# Main.net
KiCad netlist of a schematic drawn in Altium Designer
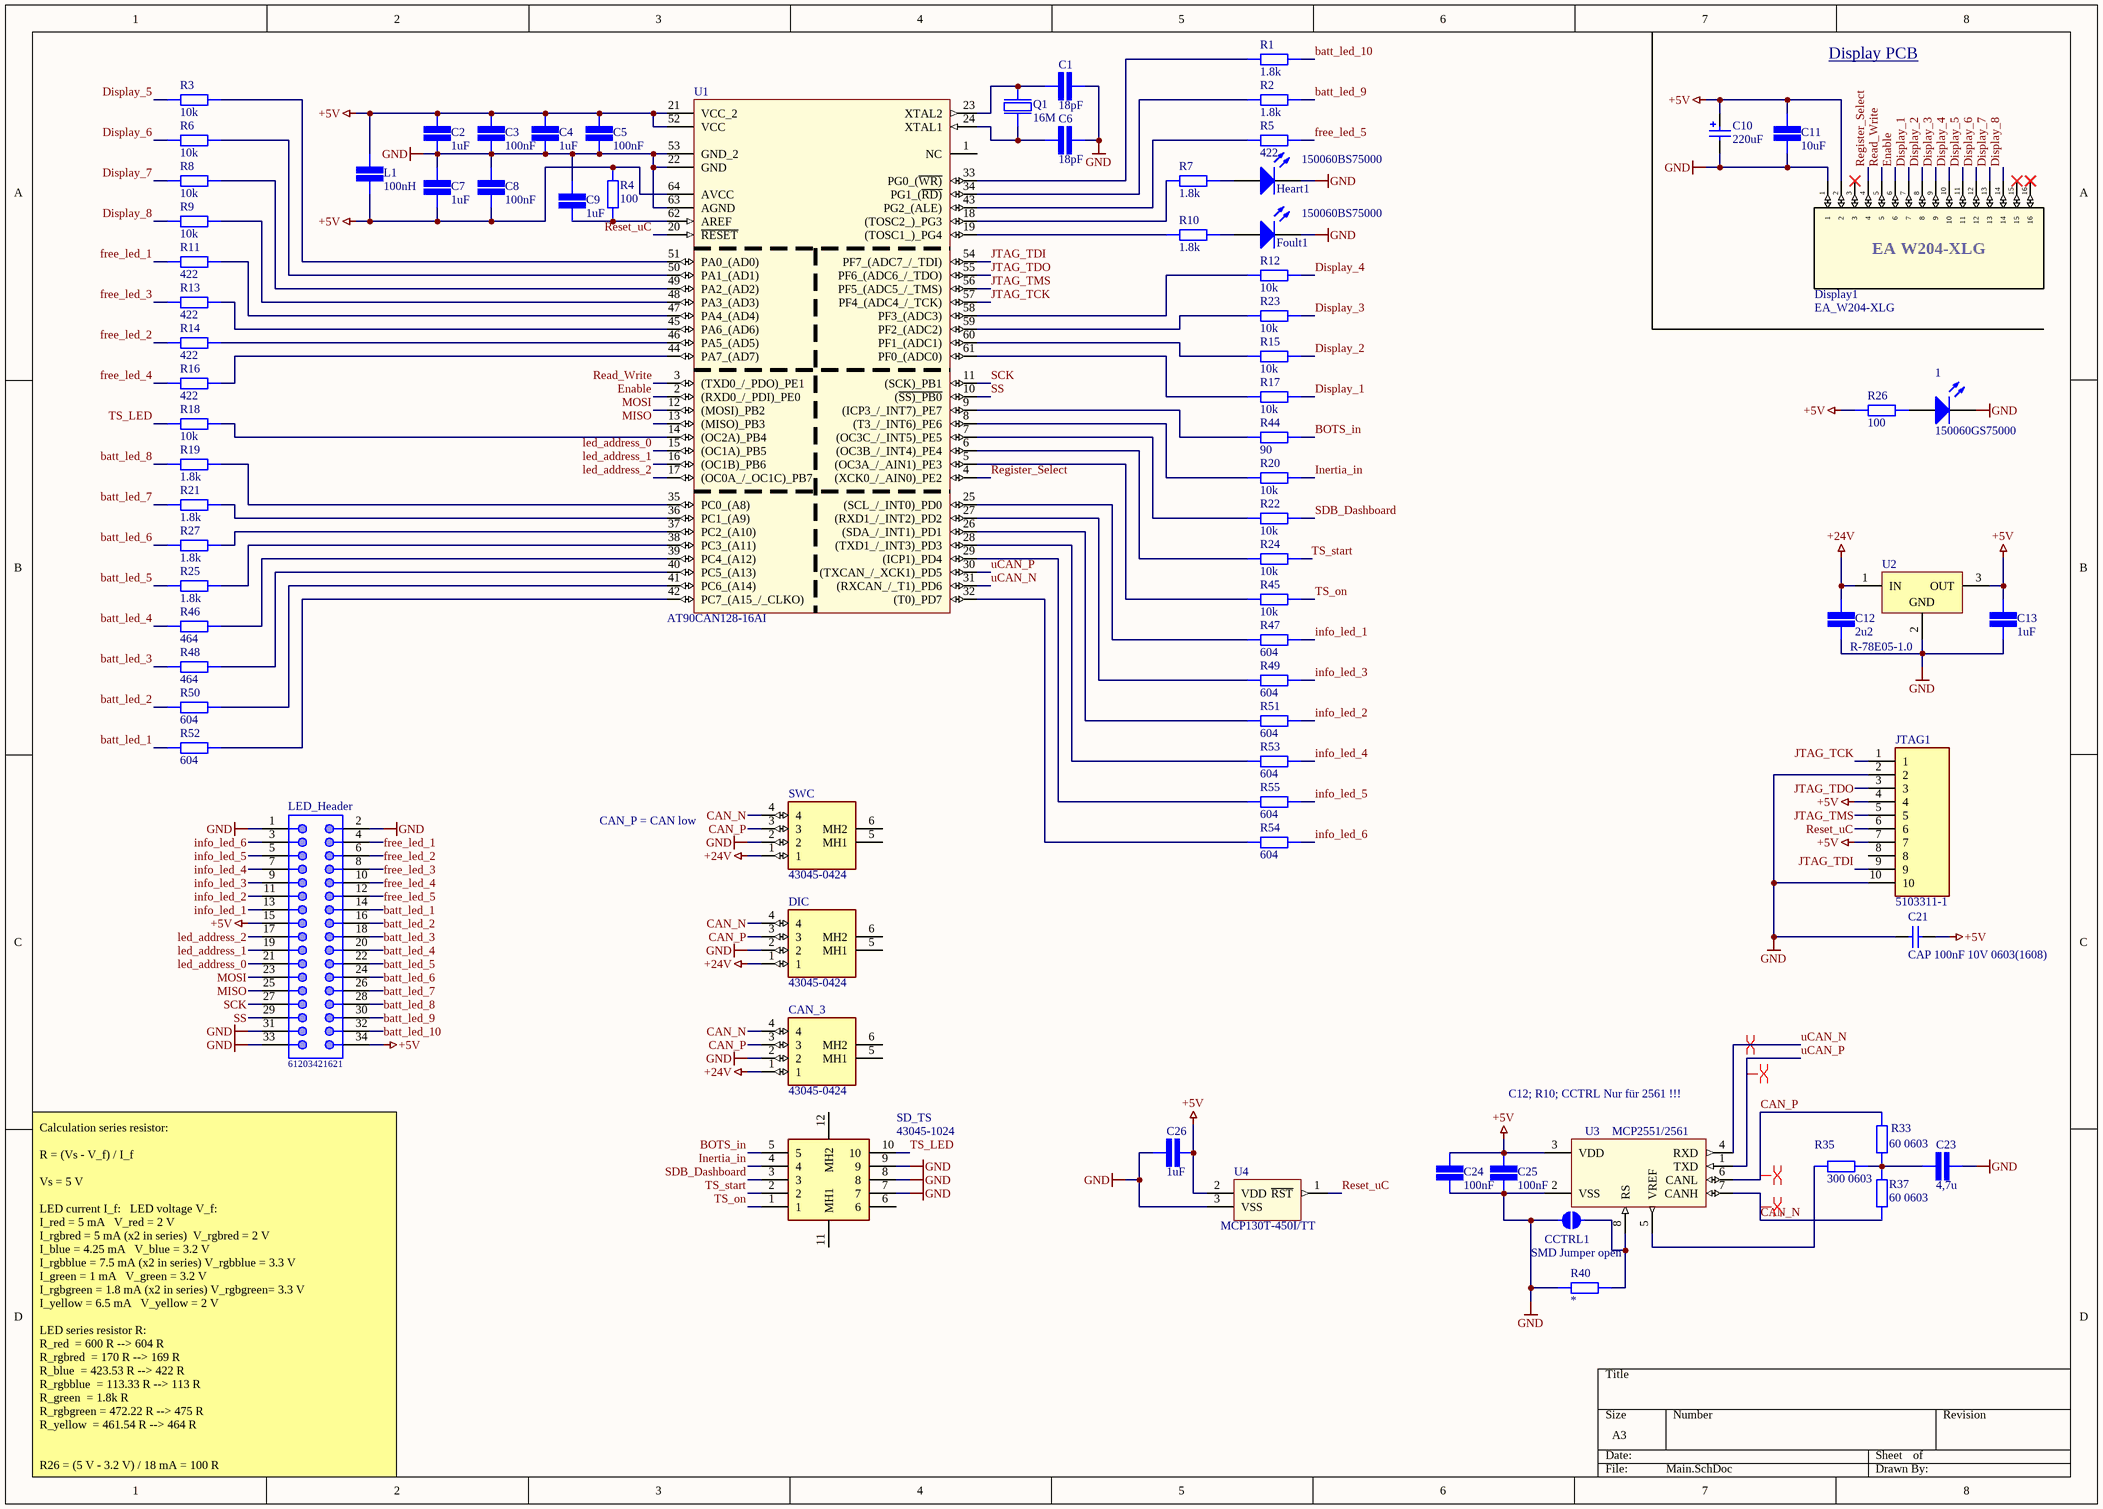
[diagram p0: Main.SchDoc]

(export (version "E")
  (design (tool "Eeschema 10.0.6"))
  (components
    (comp (ref "1")
      (value "150060GS75000")
      (footprint "0603_A")
      (description "SMD mono-color Chip LED, WL-SMCW, Green")
      (fields (field (name "MANUFACTURER") "Wuerth Elektronik"))
      (libsource (lib "Altium Content Vault") (part "WE-LED_K1A2-2"))
    )
    (comp (ref "C1")
      (value "18pF")
      (footprint "CAP 0603/1608")
      (description "Capacitor with multiple Footprints")
      (fields (field (name "Comment") "SMD Capacitor"))
      (libsource (lib "") (part "SMD Capacitor_2"))
    )
    (comp (ref "C2")
      (value "1uF")
      (footprint "CAP 0603/1608")
      (description "Capacitor with multiple Footprints")
      (fields (field (name "Comment") "SMD Capacitor"))
      (libsource (lib "Standardbauteile") (part "SMD Capacitor"))
    )
    (comp (ref "C3")
      (value "100nF")
      (footprint "CAP 0603/1608")
      (description "Capacitor with multiple Footprints")
      (fields (field (name "Comment") "SMD Capacitor"))
      (libsource (lib "Standardbauteile") (part "SMD Capacitor"))
    )
    (comp (ref "C4")
      (value "1uF")
      (footprint "CAP 0603/1608")
      (description "Capacitor with multiple Footprints")
      (fields (field (name "Comment") "SMD Capacitor"))
      (libsource (lib "Standardbauteile") (part "SMD Capacitor"))
    )
    (comp (ref "C5")
      (value "100nF")
      (footprint "CAP 0603/1608")
      (description "Capacitor with multiple Footprints")
      (fields (field (name "Comment") "SMD Capacitor"))
      (libsource (lib "Standardbauteile") (part "SMD Capacitor"))
    )
    (comp (ref "C6")
      (value "18pF")
      (footprint "CAP 0603/1608")
      (description "Capacitor with multiple Footprints")
      (fields (field (name "Comment") "SMD Capacitor"))
      (libsource (lib "") (part "SMD Capacitor_2"))
    )
    (comp (ref "C7")
      (value "1uF")
      (footprint "CAP 0603/1608")
      (description "Capacitor with multiple Footprints")
      (fields (field (name "Comment") "SMD Capacitor"))
      (libsource (lib "Standardbauteile") (part "SMD Capacitor"))
    )
    (comp (ref "C8")
      (value "100nF")
      (footprint "CAP 0603/1608")
      (description "Capacitor with multiple Footprints")
      (fields (field (name "Comment") "SMD Capacitor"))
      (libsource (lib "Standardbauteile") (part "SMD Capacitor"))
    )
    (comp (ref "C9")
      (value "1uF")
      (footprint "CAP 0603/1608")
      (description "Capacitor with multiple Footprints")
      (fields (field (name "Comment") "SMD Capacitor"))
      (libsource (lib "Standardbauteile") (part "SMD Capacitor"))
    )
    (comp (ref "C10")
      (value "220uF")
      (footprint "WCAP-ASLL_8x10.5")
      (description "WCAP-ASLL Aluminum Electrolytic Capacitors, size Ф8x10.5mm, 25V DC, 220uF")
      (fields (field (name "PART NUMBER") "865060453007") (field (name "PUBLISHER") "Wurth Elektronik"))
      (libsource (lib "ALTIUM-WCAP-ASLL-rev17a") (part "865060453007"))
    )
    (comp (ref "C11")
      (value "10uF")
      (footprint "CAP 0603/1608")
      (description "Capacitor with multiple Footprints")
      (fields (field (name "Comment") "SMD Capacitor"))
      (libsource (lib "") (part "SMD Capacitor_1"))
    )
    (comp (ref "C12")
      (value "2u2")
      (footprint "CAP 0603/1608")
      (description "Capacitor with multiple Footprints")
      (fields (field (name "Comment") "SMD Capacitor"))
      (libsource (lib "Standardbauteile") (part "SMD Capacitor"))
    )
    (comp (ref "C13")
      (value "1uF")
      (footprint "CAP 0603/1608")
      (description "Capacitor with multiple Footprints")
      (fields (field (name "Comment") "SMD Capacitor"))
      (libsource (lib "Standardbauteile") (part "SMD Capacitor"))
    )
    (comp (ref "C21")
      (value "CAP 100nF 10V 0603(1608)")
      (footprint "CAPC0603(1608)100_L")
      (description "CAP 100nF 10V ±5% 0603 (1608 Metric) Thickness 1mm SMD")
      (fields (field (name "TOLERANCE") "Â±5%"))
      (libsource (lib "Altium Content Vault") (part "CAP"))
    )
    (comp (ref "C23")
      (value "4,7u")
      (footprint "CAP 0603/1608")
      (description "Capacitor with multiple Footprints")
      (fields (field (name "Comment") "SMD Capacitor"))
      (libsource (lib "") (part "SMD Capacitor_3"))
    )
    (comp (ref "C24")
      (value "100nF")
      (footprint "CAP 0603/1608")
      (description "Capacitor with multiple Footprints")
      (fields (field (name "Comment") "SMD Capacitor"))
      (libsource (lib "Standardbauteile") (part "SMD Capacitor"))
    )
    (comp (ref "C25")
      (value "100nF")
      (footprint "CAP 0603/1608")
      (description "Capacitor with multiple Footprints")
      (fields (field (name "Comment") "SMD Capacitor"))
      (libsource (lib "Standardbauteile") (part "SMD Capacitor"))
    )
    (comp (ref "C26")
      (value "1uF")
      (footprint "CAP 0603/1608")
      (description "Capacitor with multiple Footprints")
      (fields (field (name "Comment") "SMD Capacitor"))
      (libsource (lib "") (part "SMD Capacitor_2"))
    )
    (comp (ref "CAN_3")
      (value "43045-0424")
      (footprint "43045-0424")
      (description "Connector Wire to Board Header 4 Position 3mm Solder Straight Thru-Hole Tray")
      (fields (field (name "MANUFACTURER") "Molex"))
      (libsource (lib "molex_43045") (part "43045-0424"))
    )
    (comp (ref "CCTRL1")
      (value "SMD Jumper open")
      (footprint "SMD-JUMPER-OPEN")
      (libsource (lib "Standardbauteile") (part "SMD Jumper open"))
    )
    (comp (ref "DIC")
      (value "43045-0424")
      (footprint "43045-0424")
      (description "Connector Wire to Board Header 4 Position 3mm Solder Straight Thru-Hole Tray")
      (fields (field (name "MANUFACTURER") "Molex"))
      (libsource (lib "molex_43045") (part "43045-0424"))
    )
    (comp (ref "Display1")
      (value "EA_W204-XLG")
      (footprint "EA_W204-XLG")
      (description "Display")
      (libsource (lib "libNico") (part "EA_W204-XLG"))
    )
    (comp (ref "Foult1")
      (value "150060BS75000")
      (footprint "0603_A")
      (description "SMD mono-color Chip LED, WL-SMCW, Blue")
      (fields (field (name "MANUFACTURER") "Wuerth Elektronik"))
      (libsource (lib "Altium Content Vault") (part "WE-LED_K1A2-2"))
    )
    (comp (ref "Heart1")
      (value "150060BS75000")
      (footprint "0603_A")
      (description "SMD mono-color Chip LED, WL-SMCW, Blue")
      (fields (field (name "MANUFACTURER") "Wuerth Elektronik"))
      (libsource (lib "Altium Content Vault") (part "WE-LED_K1A2-2"))
    )
    (comp (ref "JTAG1")
      (value "5103311-1")
      (footprint "TE_5103311-1")
      (description "AMP-LATCH Pin Header, Low Profile, 10 Pos., Right Angle PCB Mount, .100 X .100")
      (fields (field (name "MF") "TE Connectivity"))
      (libsource (lib "5103311-1") (part "5103311-1"))
    )
    (comp (ref "L1")
      (value "100nH")
      (footprint "CAP 0603/1608")
      (description "Capacitor with multiple Footprints")
      (fields (field (name "Comment") "SMD Capacitor"))
      (libsource (lib "Standardbauteile") (part "SMD Capacitor"))
    )
    (comp (ref "LED_Header")
      (value "61203421621")
      (footprint "61203421621")
      (description "WR-BHD Box Header, Male PCB side, pitch 2.54mm, THT, Straight, 34p")
      (fields (field (name "MANUFACTURER") "Wurth Elektronik"))
      (libsource (lib "Altium_WR-BHD (rev21a)") (part "61203421621"))
    )
    (comp (ref "Q1")
      (value "16M")
      (footprint "NDK NX5032GA")
      (description "16 MHz Quartz")
      (libsource (lib "Standardbauteile") (part "16 MHz Quartz"))
    )
    (comp (ref "R1")
      (value "1.8k")
      (footprint "STACKPOLE CSR0603")
      (description "Resistor with multiple footprints\r\n\r\n500R or 1kR depends on luminous intensity")
      (fields (field (name "Comment") "SMD Resistor"))
      (libsource (lib "Standardbauteile") (part "SMD Resistor"))
    )
    (comp (ref "R2")
      (value "1.8k")
      (footprint "STACKPOLE CSR0603")
      (description "Resistor with multiple footprints\r\n\r\n500R or 1kR depends on luminous intensity")
      (fields (field (name "Comment") "SMD Resistor"))
      (libsource (lib "Standardbauteile") (part "SMD Resistor"))
    )
    (comp (ref "R3")
      (value "10k")
      (footprint "STACKPOLE CSR0603")
      (description "Resistor with multiple footprints")
      (fields (field (name "Comment") "SMD Resistor"))
      (libsource (lib "Standardbauteile") (part "SMD Resistor"))
    )
    (comp (ref "R4")
      (value "100")
      (footprint "STACKPOLE CSR0603")
      (description "Resistor with multiple footprints")
      (fields (field (name "Comment") "SMD Resistor"))
      (libsource (lib "Standardbauteile") (part "SMD Resistor"))
    )
    (comp (ref "R5")
      (value "422")
      (footprint "STACKPOLE CSR0603")
      (description "Resistor with multiple footprints\r\n\r\n500R or 1kR depends on luminous intensity")
      (fields (field (name "Comment") "SMD Resistor"))
      (libsource (lib "Standardbauteile") (part "SMD Resistor"))
    )
    (comp (ref "R6")
      (value "10k")
      (footprint "STACKPOLE CSR0603")
      (description "Resistor with multiple footprints")
      (fields (field (name "Comment") "SMD Resistor"))
      (libsource (lib "Standardbauteile") (part "SMD Resistor"))
    )
    (comp (ref "R7")
      (value "1.8k")
      (footprint "STACKPOLE CSR0603")
      (description "Resistor with multiple footprints")
      (fields (field (name "Comment") "SMD Resistor"))
      (libsource (lib "Standardbauteile") (part "SMD Resistor"))
    )
    (comp (ref "R8")
      (value "10k")
      (footprint "STACKPOLE CSR0603")
      (description "Resistor with multiple footprints")
      (fields (field (name "Comment") "SMD Resistor"))
      (libsource (lib "Standardbauteile") (part "SMD Resistor"))
    )
    (comp (ref "R9")
      (value "10k")
      (footprint "STACKPOLE CSR0603")
      (description "Resistor with multiple footprints")
      (fields (field (name "Comment") "SMD Resistor"))
      (libsource (lib "Standardbauteile") (part "SMD Resistor"))
    )
    (comp (ref "R10")
      (value "1.8k")
      (footprint "STACKPOLE CSR0603")
      (description "Resistor with multiple footprints")
      (fields (field (name "Comment") "SMD Resistor"))
      (libsource (lib "Standardbauteile") (part "SMD Resistor"))
    )
    (comp (ref "R11")
      (value "422")
      (footprint "STACKPOLE CSR0603")
      (description "Resistor with multiple footprints\r\n\r\n500R or 1kR depends on luminous intensity")
      (fields (field (name "Comment") "SMD Resistor"))
      (libsource (lib "Standardbauteile") (part "SMD Resistor"))
    )
    (comp (ref "R12")
      (value "10k")
      (footprint "STACKPOLE CSR0603")
      (description "Resistor with multiple footprints")
      (fields (field (name "Comment") "SMD Resistor"))
      (libsource (lib "Standardbauteile") (part "SMD Resistor"))
    )
    (comp (ref "R13")
      (value "422")
      (footprint "STACKPOLE CSR0603")
      (description "Resistor with multiple footprints\r\n\r\n500R or 1kR depends on luminous intensity")
      (fields (field (name "Comment") "SMD Resistor"))
      (libsource (lib "Standardbauteile") (part "SMD Resistor"))
    )
    (comp (ref "R14")
      (value "422")
      (footprint "STACKPOLE CSR0603")
      (description "Resistor with multiple footprints\r\n\r\n500R or 1kR depends on luminous intensity")
      (fields (field (name "Comment") "SMD Resistor"))
      (libsource (lib "Standardbauteile") (part "SMD Resistor"))
    )
    (comp (ref "R15")
      (value "10k")
      (footprint "STACKPOLE CSR0603")
      (description "Resistor with multiple footprints")
      (fields (field (name "Comment") "SMD Resistor"))
      (libsource (lib "Standardbauteile") (part "SMD Resistor"))
    )
    (comp (ref "R16")
      (value "422")
      (footprint "STACKPOLE CSR0603")
      (description "Resistor with multiple footprints\r\n\r\n500R or 1kR depends on luminous intensity")
      (fields (field (name "Comment") "SMD Resistor"))
      (libsource (lib "Standardbauteile") (part "SMD Resistor"))
    )
    (comp (ref "R17")
      (value "10k")
      (footprint "STACKPOLE CSR0603")
      (description "Resistor with multiple footprints")
      (fields (field (name "Comment") "SMD Resistor"))
      (libsource (lib "Standardbauteile") (part "SMD Resistor"))
    )
    (comp (ref "R18")
      (value "10k")
      (footprint "STACKPOLE CSR0603")
      (description "Resistor with multiple footprints")
      (fields (field (name "Comment") "SMD Resistor"))
      (libsource (lib "Standardbauteile") (part "SMD Resistor"))
    )
    (comp (ref "R19")
      (value "1.8k")
      (footprint "STACKPOLE CSR0603")
      (description "Resistor with multiple footprints\r\n\r\n500R or 1kR depends on luminous intensity")
      (fields (field (name "Comment") "SMD Resistor"))
      (libsource (lib "Standardbauteile") (part "SMD Resistor"))
    )
    (comp (ref "R20")
      (value "10k")
      (footprint "STACKPOLE CSR0603")
      (description "Resistor with multiple footprints")
      (fields (field (name "Comment") "SMD Resistor"))
      (libsource (lib "Standardbauteile") (part "SMD Resistor"))
    )
    (comp (ref "R21")
      (value "1.8k")
      (footprint "STACKPOLE CSR0603")
      (description "Resistor with multiple footprints\r\n\r\n500R or 1kR depends on luminous intensity")
      (fields (field (name "Comment") "SMD Resistor"))
      (libsource (lib "Standardbauteile") (part "SMD Resistor"))
    )
    (comp (ref "R22")
      (value "10k")
      (footprint "STACKPOLE CSR0603")
      (description "Resistor with multiple footprints")
      (fields (field (name "Comment") "SMD Resistor"))
      (libsource (lib "Standardbauteile") (part "SMD Resistor"))
    )
    (comp (ref "R23")
      (value "10k")
      (footprint "STACKPOLE CSR0603")
      (description "Resistor with multiple footprints")
      (fields (field (name "Comment") "SMD Resistor"))
      (libsource (lib "Standardbauteile") (part "SMD Resistor"))
    )
    (comp (ref "R24")
      (value "10k")
      (footprint "STACKPOLE CSR0603")
      (description "Resistor with multiple footprints")
      (fields (field (name "Comment") "SMD Resistor"))
      (libsource (lib "Standardbauteile") (part "SMD Resistor"))
    )
    (comp (ref "R25")
      (value "1.8k")
      (footprint "STACKPOLE CSR0603")
      (description "Resistor with multiple footprints\r\n\r\n500R or 1kR depends on luminous intensity")
      (fields (field (name "Comment") "SMD Resistor"))
      (libsource (lib "Standardbauteile") (part "SMD Resistor"))
    )
    (comp (ref "R26")
      (value "100")
      (footprint "STACKPOLE CSR0603")
      (description "Resistor with multiple footprints")
      (fields (field (name "Comment") "SMD Resistor"))
      (libsource (lib "Standardbauteile") (part "SMD Resistor"))
    )
    (comp (ref "R27")
      (value "1.8k")
      (footprint "STACKPOLE CSR0603")
      (description "Resistor with multiple footprints\r\n\r\n500R or 1kR depends on luminous intensity")
      (fields (field (name "Comment") "SMD Resistor"))
      (libsource (lib "Standardbauteile") (part "SMD Resistor"))
    )
    (comp (ref "R33")
      (value "60 0603")
      (footprint "STACKPOLE CSR0603")
      (description "Resistor with multiple footprints")
      (fields (field (name "Comment") "SMD Resistor"))
      (libsource (lib "Standardbauteile") (part "SMD Resistor"))
    )
    (comp (ref "R35")
      (value "300 0603")
      (footprint "STACKPOLE CSR0603")
      (description "Resistor with multiple footprints")
      (fields (field (name "Comment") "SMD Resistor"))
      (libsource (lib "Standardbauteile") (part "SMD Resistor"))
    )
    (comp (ref "R37")
      (value "60 0603")
      (footprint "STACKPOLE CSR0603")
      (description "Resistor with multiple footprints")
      (fields (field (name "Comment") "SMD Resistor"))
      (libsource (lib "Standardbauteile") (part "SMD Resistor"))
    )
    (comp (ref "R40")
      (value "SMD Resistor")
      (footprint "STACKPOLE CSR0603")
      (description "Resistor with multiple footprints")
      (fields (field (name "ALTIUM_VALUE") "*"))
      (libsource (lib "Standardbauteile") (part "SMD Resistor"))
    )
    (comp (ref "R44")
      (value "90")
      (footprint "STACKPOLE CSR0603")
      (description "Resistor with multiple footprints\r\n\r\n500R or 1kR depends on luminous intensity")
      (fields (field (name "Comment") "SMD Resistor"))
      (libsource (lib "Standardbauteile") (part "SMD Resistor"))
    )
    (comp (ref "R45")
      (value "10k")
      (footprint "STACKPOLE CSR0603")
      (description "Resistor with multiple footprints")
      (fields (field (name "Comment") "SMD Resistor"))
      (libsource (lib "Standardbauteile") (part "SMD Resistor"))
    )
    (comp (ref "R46")
      (value "464")
      (footprint "STACKPOLE CSR0603")
      (description "Resistor with multiple footprints\r\n\r\n500R or 1kR depends on luminous intensity")
      (fields (field (name "Comment") "SMD Resistor"))
      (libsource (lib "Standardbauteile") (part "SMD Resistor"))
    )
    (comp (ref "R47")
      (value "604")
      (footprint "STACKPOLE CSR0603")
      (description "Resistor with multiple footprints")
      (fields (field (name "Comment") "SMD Resistor"))
      (libsource (lib "Standardbauteile") (part "SMD Resistor"))
    )
    (comp (ref "R48")
      (value "464")
      (footprint "STACKPOLE CSR0603")
      (description "Resistor with multiple footprints\r\n\r\n500R or 1kR depends on luminous intensity")
      (fields (field (name "Comment") "SMD Resistor"))
      (libsource (lib "Standardbauteile") (part "SMD Resistor"))
    )
    (comp (ref "R49")
      (value "604")
      (footprint "STACKPOLE CSR0603")
      (description "Resistor with multiple footprints")
      (fields (field (name "Comment") "SMD Resistor"))
      (libsource (lib "Standardbauteile") (part "SMD Resistor"))
    )
    (comp (ref "R50")
      (value "604")
      (footprint "STACKPOLE CSR0603")
      (description "Resistor with multiple footprints\r\n\r\n500R or 1kR depends on luminous intensity")
      (fields (field (name "Comment") "SMD Resistor"))
      (libsource (lib "Standardbauteile") (part "SMD Resistor"))
    )
    (comp (ref "R51")
      (value "604")
      (footprint "STACKPOLE CSR0603")
      (description "Resistor with multiple footprints")
      (fields (field (name "Comment") "SMD Resistor"))
      (libsource (lib "Standardbauteile") (part "SMD Resistor"))
    )
    (comp (ref "R52")
      (value "604")
      (footprint "STACKPOLE CSR0603")
      (description "Resistor with multiple footprints\r\n\r\n500R or 1kR depends on luminous intensity")
      (fields (field (name "Comment") "SMD Resistor"))
      (libsource (lib "Standardbauteile") (part "SMD Resistor"))
    )
    (comp (ref "R53")
      (value "604")
      (footprint "STACKPOLE CSR0603")
      (description "Resistor with multiple footprints")
      (fields (field (name "Comment") "SMD Resistor"))
      (libsource (lib "Standardbauteile") (part "SMD Resistor"))
    )
    (comp (ref "R54")
      (value "604")
      (footprint "STACKPOLE CSR0603")
      (description "Resistor with multiple footprints")
      (fields (field (name "Comment") "SMD Resistor"))
      (libsource (lib "Standardbauteile") (part "SMD Resistor"))
    )
    (comp (ref "R55")
      (value "604")
      (footprint "STACKPOLE CSR0603")
      (description "Resistor with multiple footprints")
      (fields (field (name "Comment") "SMD Resistor"))
      (libsource (lib "Standardbauteile") (part "SMD Resistor"))
    )
    (comp (ref "SD_TS")
      (value "43045-1024")
      (footprint "43045-1024")
      (description "Connector Wire to Board Header 10 Position 3mm Solder Straight Thru-Hole Tray")
      (fields (field (name "MANUFACTURER") "Molex"))
      (libsource (lib "molex_43045") (part "43045-1024"))
    )
    (comp (ref "SWC")
      (value "43045-0424")
      (footprint "43045-0424")
      (description "Connector Wire to Board Header 4 Position 3mm Solder Straight Thru-Hole Tray")
      (fields (field (name "MANUFACTURER") "Molex"))
      (libsource (lib "molex_43045") (part "43045-0424"))
    )
    (comp (ref "U1")
      (value "AT90CAN128-16AI")
      (footprint "*QFP80P1600X1600X120-64N")
      (description "Ic Mcu 8bit 128kb Flash 64tqfp")
      (fields (field (name "MF") "Microchip"))
      (libsource (lib "Eric") (part "AT90CAN128-16AI"))
    )
    (comp (ref "U2")
      (value "R-78E05-1.0")
      (footprint "SIP3_RECOM")
      (description "Nonisolated 5V Switchmode converter")
      (libsource (lib "Standardbauteile") (part "R-78E05-1.0"))
    )
    (comp (ref "U3")
      (value "MCP2551/2561")
      (footprint "*SOIC127P600X175-8N")
      (description "MCP2551 Series 5.5 V 1 Mb/s Surface Mount High-Speed CAN Transceiver - SOIC-8")
      (fields (field (name "MP") "MCP2551-I/SN") (field (name "MF") "Microchip"))
      (libsource (lib "Eric") (part "MCP2551-I/SN"))
    )
    (comp (ref "U4")
      (value "MCP130T-450I/TT")
      (footprint "*SOT95P237X112-3N")
      (description "System Supervisors - Power Supply Monitors with Reset Generators Open Drain Low")
      (fields (field (name "MF") "Microchip") (field (name "MP") "MCP120T-450I/TT"))
      (libsource (lib "Eric") (part "MCP130T-450I/TT"))
    )
  )
  (nets
    (net (code "1") (name "+5V") (class "Default")
      (node (ref "C10") (pin "1") (pinfunction "P_1") (pintype "passive"))
      (node (ref "C11") (pin "1") (pinfunction "1_1") (pintype "passive"))
      (node (ref "C13") (pin "2") (pinfunction "2_2") (pintype "passive"))
      (node (ref "C2") (pin "2") (pinfunction "2_2") (pintype "passive"))
      (node (ref "C21") (pin "1") (pinfunction "1_1") (pintype "passive"))
      (node (ref "C24") (pin "2") (pinfunction "2_2") (pintype "passive"))
      (node (ref "C25") (pin "2") (pinfunction "2_2") (pintype "passive"))
      (node (ref "C26") (pin "1") (pinfunction "1_1") (pintype "passive"))
      (node (ref "C3") (pin "2") (pinfunction "2_2") (pintype "passive"))
      (node (ref "C4") (pin "2") (pinfunction "2_2") (pintype "passive"))
      (node (ref "C5") (pin "2") (pinfunction "2_2") (pintype "passive"))
      (node (ref "C7") (pin "1") (pinfunction "1_1") (pintype "passive"))
      (node (ref "C8") (pin "1") (pinfunction "1_1") (pintype "passive"))
      (node (ref "Display1") (pin "2") (pinfunction "2_2") (pintype "bidirectional"))
      (node (ref "JTAG1") (pin "4") (pinfunction "4_4") (pintype "passive"))
      (node (ref "JTAG1") (pin "7") (pinfunction "7_7") (pintype "passive"))
      (node (ref "L1") (pin "1") (pinfunction "1_1") (pintype "passive"))
      (node (ref "L1") (pin "2") (pinfunction "2_2") (pintype "passive"))
      (node (ref "LED_Header") (pin "15") (pinfunction "15_15") (pintype "passive"))
      (node (ref "LED_Header") (pin "34") (pinfunction "34_34") (pintype "passive"))
      (node (ref "R26") (pin "1") (pinfunction "1_1") (pintype "passive"))
      (node (ref "R4") (pin "2") (pinfunction "2_2") (pintype "passive"))
      (node (ref "U1") (pin "21") (pinfunction "VCC_2_21") (pintype "power_in"))
      (node (ref "U1") (pin "52") (pinfunction "VCC_52") (pintype "power_in"))
      (node (ref "U1") (pin "64") (pinfunction "AVCC_64") (pintype "power_in"))
      (node (ref "U2") (pin "3") (pinfunction "OUT_3") (pintype "power_in"))
      (node (ref "U3") (pin "3") (pinfunction "VDD_3") (pintype "power_in"))
      (node (ref "U4") (pin "2") (pinfunction "VDD_2") (pintype "power_in"))
    )
    (net (code "2") (name "+24V") (class "Default")
      (node (ref "C12") (pin "2") (pinfunction "2_2") (pintype "passive"))
      (node (ref "CAN_3") (pin "1") (pinfunction "1_1") (pintype "bidirectional"))
      (node (ref "DIC") (pin "1") (pinfunction "1_1") (pintype "bidirectional"))
      (node (ref "SWC") (pin "1") (pinfunction "1_1") (pintype "bidirectional"))
      (node (ref "U2") (pin "1") (pinfunction "IN_1") (pintype "power_in"))
    )
    (net (code "3") (name "/BOTS_in") (class "Default")
      (node (ref "R44") (pin "2") (pinfunction "2_2") (pintype "passive"))
      (node (ref "SD_TS") (pin "5") (pinfunction "5_5") (pintype "passive"))
    )
    (net (code "4") (name "/CAN_N") (class "Default")
      (node (ref "CAN_3") (pin "4") (pinfunction "4_4") (pintype "bidirectional"))
      (node (ref "DIC") (pin "4") (pinfunction "4_4") (pintype "bidirectional"))
      (node (ref "R37") (pin "2") (pinfunction "2_2") (pintype "passive"))
      (node (ref "SWC") (pin "4") (pinfunction "4_4") (pintype "bidirectional"))
      (node (ref "U3") (pin "7") (pinfunction "CANH_7") (pintype "bidirectional"))
    )
    (net (code "5") (name "/CAN_P") (class "Default")
      (node (ref "CAN_3") (pin "3") (pinfunction "3_3") (pintype "bidirectional"))
      (node (ref "DIC") (pin "3") (pinfunction "3_3") (pintype "bidirectional"))
      (node (ref "R33") (pin "1") (pinfunction "1_1") (pintype "passive"))
      (node (ref "SWC") (pin "3") (pinfunction "3_3") (pintype "bidirectional"))
      (node (ref "U3") (pin "6") (pinfunction "CANL_6") (pintype "bidirectional"))
    )
    (net (code "6") (name "/Display_1") (class "Default")
      (node (ref "Display1") (pin "7") (pinfunction "7_7") (pintype "bidirectional"))
      (node (ref "R17") (pin "1") (pinfunction "1_1") (pintype "passive"))
    )
    (net (code "7") (name "/Display_2") (class "Default")
      (node (ref "Display1") (pin "8") (pinfunction "8_8") (pintype "bidirectional"))
      (node (ref "R15") (pin "1") (pinfunction "1_1") (pintype "passive"))
    )
    (net (code "8") (name "/Display_3") (class "Default")
      (node (ref "Display1") (pin "9") (pinfunction "9_9") (pintype "bidirectional"))
      (node (ref "R23") (pin "2") (pinfunction "2_2") (pintype "passive"))
    )
    (net (code "9") (name "/Display_4") (class "Default")
      (node (ref "Display1") (pin "10") (pinfunction "10_10") (pintype "bidirectional"))
      (node (ref "R12") (pin "1") (pinfunction "1_1") (pintype "passive"))
    )
    (net (code "10") (name "/Display_5") (class "Default")
      (node (ref "Display1") (pin "11") (pinfunction "11_11") (pintype "bidirectional"))
      (node (ref "R3") (pin "1") (pinfunction "1_1") (pintype "passive"))
    )
    (net (code "11") (name "/Display_6") (class "Default")
      (node (ref "Display1") (pin "12") (pinfunction "12_12") (pintype "bidirectional"))
      (node (ref "R6") (pin "1") (pinfunction "1_1") (pintype "passive"))
    )
    (net (code "12") (name "/Display_7") (class "Default")
      (node (ref "Display1") (pin "13") (pinfunction "13_13") (pintype "bidirectional"))
      (node (ref "R8") (pin "1") (pinfunction "1_1") (pintype "passive"))
    )
    (net (code "13") (name "/Display_8") (class "Default")
      (node (ref "Display1") (pin "14") (pinfunction "14_14") (pintype "bidirectional"))
      (node (ref "R9") (pin "1") (pinfunction "1_1") (pintype "passive"))
    )
    (net (code "14") (name "/Enable") (class "Default")
      (node (ref "Display1") (pin "6") (pinfunction "6_6") (pintype "bidirectional"))
      (node (ref "U1") (pin "2") (pinfunction "(RXD0_/_PDI)_PE0_2") (pintype "bidirectional"))
    )
    (net (code "15") (name "/Inertia_in") (class "Default")
      (node (ref "R20") (pin "1") (pinfunction "1_1") (pintype "passive"))
      (node (ref "SD_TS") (pin "4") (pinfunction "4_4") (pintype "passive"))
    )
    (net (code "16") (name "/JTAG_TCK") (class "Default")
      (node (ref "JTAG1") (pin "1") (pinfunction "1_1") (pintype "passive"))
      (node (ref "U1") (pin "57") (pinfunction "PF4_(ADC4_/_TCK)_57") (pintype "bidirectional"))
    )
    (net (code "17") (name "/JTAG_TDI") (class "Default")
      (node (ref "JTAG1") (pin "9") (pinfunction "9_9") (pintype "passive"))
      (node (ref "U1") (pin "54") (pinfunction "PF7_(ADC7_/_TDI)_54") (pintype "bidirectional"))
    )
    (net (code "18") (name "/JTAG_TDO") (class "Default")
      (node (ref "JTAG1") (pin "3") (pinfunction "3_3") (pintype "passive"))
      (node (ref "U1") (pin "55") (pinfunction "PF6_(ADC6_/_TDO)_55") (pintype "bidirectional"))
    )
    (net (code "19") (name "/JTAG_TMS") (class "Default")
      (node (ref "JTAG1") (pin "5") (pinfunction "5_5") (pintype "passive"))
      (node (ref "U1") (pin "56") (pinfunction "PF5_(ADC5_/_TMS)_56") (pintype "bidirectional"))
    )
    (net (code "20") (name "/MISO") (class "Default")
      (node (ref "LED_Header") (pin "25") (pinfunction "25_25") (pintype "passive"))
      (node (ref "U1") (pin "13") (pinfunction "(MISO)_PB3_13") (pintype "bidirectional"))
    )
    (net (code "21") (name "/MOSI") (class "Default")
      (node (ref "LED_Header") (pin "23") (pinfunction "23_23") (pintype "passive"))
      (node (ref "U1") (pin "12") (pinfunction "(MOSI)_PB2_12") (pintype "bidirectional"))
    )
    (net (code "22") (name "/Read_Write") (class "Default")
      (node (ref "Display1") (pin "5") (pinfunction "5_5") (pintype "bidirectional"))
      (node (ref "U1") (pin "3") (pinfunction "(TXD0_/_PDO)_PE1_3") (pintype "bidirectional"))
    )
    (net (code "23") (name "/Register_Select") (class "Default")
      (node (ref "Display1") (pin "4") (pinfunction "4_4") (pintype "bidirectional"))
      (node (ref "U1") (pin "4") (pinfunction "(XCK0_/_AIN0)_PE2_4") (pintype "bidirectional"))
    )
    (net (code "24") (name "/Reset_uC") (class "Default")
      (node (ref "JTAG1") (pin "6") (pinfunction "6_6") (pintype "passive"))
      (node (ref "U1") (pin "20") (pinfunction "~{RESET}_20") (pintype "input"))
      (node (ref "U4") (pin "1") (pinfunction "~{RST}_1") (pintype "output"))
    )
    (net (code "25") (name "/SCK") (class "Default")
      (node (ref "LED_Header") (pin "27") (pinfunction "27_27") (pintype "passive"))
      (node (ref "U1") (pin "11") (pinfunction "(SCK)_PB1_11") (pintype "bidirectional"))
    )
    (net (code "26") (name "/SDB_Dashboard") (class "Default")
      (node (ref "R22") (pin "2") (pinfunction "2_2") (pintype "passive"))
      (node (ref "SD_TS") (pin "3") (pinfunction "3_3") (pintype "passive"))
    )
    (net (code "27") (name "/SS") (class "Default")
      (node (ref "LED_Header") (pin "29") (pinfunction "29_29") (pintype "passive"))
      (node (ref "U1") (pin "10") (pinfunction "(~{SS)_PB0}_10") (pintype "bidirectional"))
    )
    (net (code "28") (name "/TS_LED") (class "Default")
      (node (ref "R18") (pin "1") (pinfunction "1_1") (pintype "passive"))
      (node (ref "SD_TS") (pin "10") (pinfunction "10_10") (pintype "passive"))
    )
    (net (code "29") (name "/TS_on") (class "Default")
      (node (ref "R45") (pin "1") (pinfunction "1_1") (pintype "passive"))
      (node (ref "SD_TS") (pin "1") (pinfunction "1_1") (pintype "passive"))
    )
    (net (code "30") (name "/TS_start") (class "Default")
      (node (ref "R24") (pin "1") (pinfunction "1_1") (pintype "passive"))
      (node (ref "SD_TS") (pin "2") (pinfunction "2_2") (pintype "passive"))
    )
    (net (code "31") (name "/batt_led_1") (class "Default")
      (node (ref "LED_Header") (pin "14") (pinfunction "14_14") (pintype "passive"))
      (node (ref "R52") (pin "1") (pinfunction "1_1") (pintype "passive"))
    )
    (net (code "32") (name "/batt_led_2") (class "Default")
      (node (ref "LED_Header") (pin "16") (pinfunction "16_16") (pintype "passive"))
      (node (ref "R50") (pin "1") (pinfunction "1_1") (pintype "passive"))
    )
    (net (code "33") (name "/batt_led_3") (class "Default")
      (node (ref "LED_Header") (pin "18") (pinfunction "18_18") (pintype "passive"))
      (node (ref "R48") (pin "1") (pinfunction "1_1") (pintype "passive"))
    )
    (net (code "34") (name "/batt_led_4") (class "Default")
      (node (ref "LED_Header") (pin "20") (pinfunction "20_20") (pintype "passive"))
      (node (ref "R46") (pin "1") (pinfunction "1_1") (pintype "passive"))
    )
    (net (code "35") (name "/batt_led_5") (class "Default")
      (node (ref "LED_Header") (pin "22") (pinfunction "22_22") (pintype "passive"))
      (node (ref "R25") (pin "2") (pinfunction "2_2") (pintype "passive"))
    )
    (net (code "36") (name "/batt_led_6") (class "Default")
      (node (ref "LED_Header") (pin "24") (pinfunction "24_24") (pintype "passive"))
      (node (ref "R27") (pin "2") (pinfunction "2_2") (pintype "passive"))
    )
    (net (code "37") (name "/batt_led_7") (class "Default")
      (node (ref "LED_Header") (pin "26") (pinfunction "26_26") (pintype "passive"))
      (node (ref "R21") (pin "1") (pinfunction "1_1") (pintype "passive"))
    )
    (net (code "38") (name "/batt_led_8") (class "Default")
      (node (ref "LED_Header") (pin "28") (pinfunction "28_28") (pintype "passive"))
      (node (ref "R19") (pin "1") (pinfunction "1_1") (pintype "passive"))
    )
    (net (code "39") (name "/batt_led_9") (class "Default")
      (node (ref "LED_Header") (pin "30") (pinfunction "30_30") (pintype "passive"))
      (node (ref "R2") (pin "1") (pinfunction "1_1") (pintype "passive"))
    )
    (net (code "40") (name "/batt_led_10") (class "Default")
      (node (ref "LED_Header") (pin "32") (pinfunction "32_32") (pintype "passive"))
      (node (ref "R1") (pin "1") (pinfunction "1_1") (pintype "passive"))
    )
    (net (code "41") (name "/free_led_1") (class "Default")
      (node (ref "LED_Header") (pin "4") (pinfunction "4_4") (pintype "passive"))
      (node (ref "R11") (pin "2") (pinfunction "2_2") (pintype "passive"))
    )
    (net (code "42") (name "/free_led_2") (class "Default")
      (node (ref "LED_Header") (pin "6") (pinfunction "6_6") (pintype "passive"))
      (node (ref "R14") (pin "2") (pinfunction "2_2") (pintype "passive"))
    )
    (net (code "43") (name "/free_led_3") (class "Default")
      (node (ref "LED_Header") (pin "8") (pinfunction "8_8") (pintype "passive"))
      (node (ref "R13") (pin "2") (pinfunction "2_2") (pintype "passive"))
    )
    (net (code "44") (name "/free_led_4") (class "Default")
      (node (ref "LED_Header") (pin "10") (pinfunction "10_10") (pintype "passive"))
      (node (ref "R16") (pin "2") (pinfunction "2_2") (pintype "passive"))
    )
    (net (code "45") (name "/free_led_5") (class "Default")
      (node (ref "LED_Header") (pin "12") (pinfunction "12_12") (pintype "passive"))
      (node (ref "R5") (pin "1") (pinfunction "1_1") (pintype "passive"))
    )
    (net (code "46") (name "/info_led_1") (class "Default")
      (node (ref "LED_Header") (pin "13") (pinfunction "13_13") (pintype "passive"))
      (node (ref "R47") (pin "2") (pinfunction "2_2") (pintype "passive"))
    )
    (net (code "47") (name "/info_led_2") (class "Default")
      (node (ref "LED_Header") (pin "11") (pinfunction "11_11") (pintype "passive"))
      (node (ref "R51") (pin "2") (pinfunction "2_2") (pintype "passive"))
    )
    (net (code "48") (name "/info_led_3") (class "Default")
      (node (ref "LED_Header") (pin "9") (pinfunction "9_9") (pintype "passive"))
      (node (ref "R49") (pin "1") (pinfunction "1_1") (pintype "passive"))
    )
    (net (code "49") (name "/info_led_4") (class "Default")
      (node (ref "LED_Header") (pin "7") (pinfunction "7_7") (pintype "passive"))
      (node (ref "R53") (pin "2") (pinfunction "2_2") (pintype "passive"))
    )
    (net (code "50") (name "/info_led_5") (class "Default")
      (node (ref "LED_Header") (pin "5") (pinfunction "5_5") (pintype "passive"))
      (node (ref "R55") (pin "2") (pinfunction "2_2") (pintype "passive"))
    )
    (net (code "51") (name "/info_led_6") (class "Default")
      (node (ref "LED_Header") (pin "3") (pinfunction "3_3") (pintype "passive"))
      (node (ref "R54") (pin "2") (pinfunction "2_2") (pintype "passive"))
    )
    (net (code "52") (name "/led_address_0") (class "Default")
      (node (ref "LED_Header") (pin "21") (pinfunction "21_21") (pintype "passive"))
      (node (ref "U1") (pin "15") (pinfunction "(OC1A)_PB5_15") (pintype "bidirectional"))
    )
    (net (code "53") (name "/led_address_1") (class "Default")
      (node (ref "LED_Header") (pin "19") (pinfunction "19_19") (pintype "passive"))
      (node (ref "U1") (pin "16") (pinfunction "(OC1B)_PB6_16") (pintype "bidirectional"))
    )
    (net (code "54") (name "/led_address_2") (class "Default")
      (node (ref "LED_Header") (pin "17") (pinfunction "17_17") (pintype "passive"))
      (node (ref "U1") (pin "17") (pinfunction "(OC0A_/_OC1C)_PB7_17") (pintype "bidirectional"))
    )
    (net (code "55") (name "/uCAN_N") (class "Default")
      (node (ref "U1") (pin "31") (pinfunction "(RXCAN_/_T1)_PD6_31") (pintype "bidirectional"))
      (node (ref "U3") (pin "4") (pinfunction "RXD_4") (pintype "output"))
    )
    (net (code "56") (name "/uCAN_P") (class "Default")
      (node (ref "U1") (pin "30") (pinfunction "(TXCAN_/_XCK1)_PD5_30") (pintype "bidirectional"))
      (node (ref "U3") (pin "1") (pinfunction "TXD_1") (pintype "input"))
    )
    (net (code "57") (name "GND") (class "Default")
      (node (ref "1") (pin "1") (pinfunction "K_1") (pintype "passive"))
      (node (ref "C1") (pin "1") (pinfunction "1_1") (pintype "passive"))
      (node (ref "C10") (pin "2") (pinfunction "N_2") (pintype "passive"))
      (node (ref "C11") (pin "2") (pinfunction "2_2") (pintype "passive"))
      (node (ref "C12") (pin "1") (pinfunction "1_1") (pintype "passive"))
      (node (ref "C13") (pin "1") (pinfunction "1_1") (pintype "passive"))
      (node (ref "C2") (pin "1") (pinfunction "1_1") (pintype "passive"))
      (node (ref "C21") (pin "2") (pinfunction "2_2") (pintype "passive"))
      (node (ref "C23") (pin "2") (pinfunction "2_2") (pintype "passive"))
      (node (ref "C24") (pin "1") (pinfunction "1_1") (pintype "passive"))
      (node (ref "C25") (pin "1") (pinfunction "1_1") (pintype "passive"))
      (node (ref "C26") (pin "2") (pinfunction "2_2") (pintype "passive"))
      (node (ref "C3") (pin "1") (pinfunction "1_1") (pintype "passive"))
      (node (ref "C4") (pin "1") (pinfunction "1_1") (pintype "passive"))
      (node (ref "C5") (pin "1") (pinfunction "1_1") (pintype "passive"))
      (node (ref "C6") (pin "1") (pinfunction "1_1") (pintype "passive"))
      (node (ref "C7") (pin "2") (pinfunction "2_2") (pintype "passive"))
      (node (ref "C8") (pin "2") (pinfunction "2_2") (pintype "passive"))
      (node (ref "C9") (pin "2") (pinfunction "2_2") (pintype "passive"))
      (node (ref "CAN_3") (pin "2") (pinfunction "2_2") (pintype "bidirectional"))
      (node (ref "CCTRL1") (pin "1") (pinfunction "1_1") (pintype "passive"))
      (node (ref "DIC") (pin "2") (pinfunction "2_2") (pintype "bidirectional"))
      (node (ref "Display1") (pin "1") (pinfunction "1_1") (pintype "bidirectional"))
      (node (ref "Foult1") (pin "1") (pinfunction "K_1") (pintype "passive"))
      (node (ref "Heart1") (pin "1") (pinfunction "K_1") (pintype "passive"))
      (node (ref "JTAG1") (pin "10") (pinfunction "10_10") (pintype "passive"))
      (node (ref "JTAG1") (pin "2") (pinfunction "2_2") (pintype "passive"))
      (node (ref "LED_Header") (pin "1") (pinfunction "1_1") (pintype "passive"))
      (node (ref "LED_Header") (pin "2") (pinfunction "2_2") (pintype "passive"))
      (node (ref "LED_Header") (pin "31") (pinfunction "31_31") (pintype "passive"))
      (node (ref "LED_Header") (pin "33") (pinfunction "33_33") (pintype "passive"))
      (node (ref "R40") (pin "1") (pinfunction "1_1") (pintype "passive"))
      (node (ref "SD_TS") (pin "7") (pinfunction "7_7") (pintype "passive"))
      (node (ref "SD_TS") (pin "8") (pinfunction "8_8") (pintype "passive"))
      (node (ref "SD_TS") (pin "9") (pinfunction "9_9") (pintype "passive"))
      (node (ref "SWC") (pin "2") (pinfunction "2_2") (pintype "bidirectional"))
      (node (ref "U1") (pin "22") (pinfunction "GND_22") (pintype "passive"))
      (node (ref "U1") (pin "53") (pinfunction "GND_2_53") (pintype "passive"))
      (node (ref "U1") (pin "63") (pinfunction "AGND_63") (pintype "passive"))
      (node (ref "U2") (pin "2") (pinfunction "GND_2") (pintype "power_in"))
      (node (ref "U3") (pin "2") (pinfunction "VSS_2") (pintype "passive"))
      (node (ref "U4") (pin "3") (pinfunction "VSS_3") (pintype "power_in"))
    )
    (net (code "58") (name "Net-(1-A)") (class "Default")
      (node (ref "1") (pin "2") (pinfunction "A_2") (pintype "passive"))
      (node (ref "R26") (pin "2") (pinfunction "2_2") (pintype "passive"))
    )
    (net (code "59") (name "Net-(C23-Pad1)") (class "Default")
      (node (ref "C23") (pin "1") (pinfunction "1_1") (pintype "passive"))
      (node (ref "R33") (pin "2") (pinfunction "2_2") (pintype "passive"))
      (node (ref "R35") (pin "2") (pinfunction "2_2") (pintype "passive"))
      (node (ref "R37") (pin "1") (pinfunction "1_1") (pintype "passive"))
    )
    (net (code "60") (name "Net-(Foult1-A)") (class "Default")
      (node (ref "Foult1") (pin "2") (pinfunction "A_2") (pintype "passive"))
      (node (ref "R10") (pin "2") (pinfunction "2_2") (pintype "passive"))
    )
    (net (code "61") (name "Net-(Heart1-A)") (class "Default")
      (node (ref "Heart1") (pin "2") (pinfunction "A_2") (pintype "passive"))
      (node (ref "R7") (pin "2") (pinfunction "2_2") (pintype "passive"))
    )
    (net (code "62") (name "Net-(U1-(ICP1)_PD4)") (class "Default")
      (node (ref "R55") (pin "1") (pinfunction "1_1") (pintype "passive"))
      (node (ref "U1") (pin "29") (pinfunction "(ICP1)_PD4_29") (pintype "bidirectional"))
    )
    (net (code "63") (name "Net-(U1-(ICP3_{slash}_INT7)_PE7)") (class "Default")
      (node (ref "R44") (pin "1") (pinfunction "1_1") (pintype "passive"))
      (node (ref "U1") (pin "9") (pinfunction "(ICP3_/_INT7)_PE7_9") (pintype "bidirectional"))
    )
    (net (code "64") (name "Net-(U1-(OC2A)_PB4)") (class "Default")
      (node (ref "R18") (pin "2") (pinfunction "2_2") (pintype "passive"))
      (node (ref "U1") (pin "14") (pinfunction "(OC2A)_PB4_14") (pintype "bidirectional"))
    )
    (net (code "65") (name "Net-(U1-(OC3A_{slash}_AIN1)_PE3)") (class "Default")
      (node (ref "R45") (pin "2") (pinfunction "2_2") (pintype "passive"))
      (node (ref "U1") (pin "5") (pinfunction "(OC3A_/_AIN1)_PE3_5") (pintype "bidirectional"))
    )
    (net (code "66") (name "Net-(U1-(OC3B_{slash}_INT4)_PE4)") (class "Default")
      (node (ref "R24") (pin "2") (pinfunction "2_2") (pintype "passive"))
      (node (ref "U1") (pin "6") (pinfunction "(OC3B_/_INT4)_PE4_6") (pintype "bidirectional"))
    )
    (net (code "67") (name "Net-(U1-(OC3C_{slash}_INT5)_PE5)") (class "Default")
      (node (ref "R22") (pin "1") (pinfunction "1_1") (pintype "passive"))
      (node (ref "U1") (pin "7") (pinfunction "(OC3C_/_INT5)_PE5_7") (pintype "bidirectional"))
    )
    (net (code "68") (name "Net-(U1-(RXD1_{slash}_INT2)_PD2)") (class "Default")
      (node (ref "R49") (pin "2") (pinfunction "2_2") (pintype "passive"))
      (node (ref "U1") (pin "27") (pinfunction "(RXD1_/_INT2)_PD2_27") (pintype "bidirectional"))
    )
    (net (code "69") (name "Net-(U1-(SCL_{slash}_INT0)_PD0)") (class "Default")
      (node (ref "R47") (pin "1") (pinfunction "1_1") (pintype "passive"))
      (node (ref "U1") (pin "25") (pinfunction "(SCL_/_INT0)_PD0_25") (pintype "bidirectional"))
    )
    (net (code "70") (name "Net-(U1-(SDA_{slash}_INT1)_PD1)") (class "Default")
      (node (ref "R51") (pin "1") (pinfunction "1_1") (pintype "passive"))
      (node (ref "U1") (pin "26") (pinfunction "(SDA_/_INT1)_PD1_26") (pintype "bidirectional"))
    )
    (net (code "71") (name "Net-(U1-(T0)_PD7)") (class "Default")
      (node (ref "R54") (pin "1") (pinfunction "1_1") (pintype "passive"))
      (node (ref "U1") (pin "32") (pinfunction "(T0)_PD7_32") (pintype "bidirectional"))
    )
    (net (code "72") (name "Net-(U1-(T3_{slash}_INT6)_PE6)") (class "Default")
      (node (ref "R20") (pin "2") (pinfunction "2_2") (pintype "passive"))
      (node (ref "U1") (pin "8") (pinfunction "(T3_/_INT6)_PE6_8") (pintype "bidirectional"))
    )
    (net (code "73") (name "Net-(U1-(TOSC1_)_PG4)") (class "Default")
      (node (ref "R10") (pin "1") (pinfunction "1_1") (pintype "passive"))
      (node (ref "U1") (pin "19") (pinfunction "(TOSC1_)_PG4_19") (pintype "bidirectional"))
    )
    (net (code "74") (name "Net-(U1-(TOSC2_)_PG3)") (class "Default")
      (node (ref "R7") (pin "1") (pinfunction "1_1") (pintype "passive"))
      (node (ref "U1") (pin "18") (pinfunction "(TOSC2_)_PG3_18") (pintype "bidirectional"))
    )
    (net (code "75") (name "Net-(U1-(TXD1_{slash}_INT3)_PD3)") (class "Default")
      (node (ref "R53") (pin "1") (pinfunction "1_1") (pintype "passive"))
      (node (ref "U1") (pin "28") (pinfunction "(TXD1_/_INT3)_PD3_28") (pintype "bidirectional"))
    )
    (net (code "76") (name "Net-(U1-AREF)") (class "Default")
      (node (ref "C9") (pin "1") (pinfunction "1_1") (pintype "passive"))
      (node (ref "R4") (pin "1") (pinfunction "1_1") (pintype "passive"))
      (node (ref "U1") (pin "62") (pinfunction "AREF_62") (pintype "input"))
    )
    (net (code "77") (name "Net-(U1-PA0_(AD0))") (class "Default")
      (node (ref "R3") (pin "2") (pinfunction "2_2") (pintype "passive"))
      (node (ref "U1") (pin "51") (pinfunction "PA0_(AD0)_51") (pintype "bidirectional"))
    )
    (net (code "78") (name "Net-(U1-PA1_(AD1))") (class "Default")
      (node (ref "R6") (pin "2") (pinfunction "2_2") (pintype "passive"))
      (node (ref "U1") (pin "50") (pinfunction "PA1_(AD1)_50") (pintype "bidirectional"))
    )
    (net (code "79") (name "Net-(U1-PA2_(AD2))") (class "Default")
      (node (ref "R8") (pin "2") (pinfunction "2_2") (pintype "passive"))
      (node (ref "U1") (pin "49") (pinfunction "PA2_(AD2)_49") (pintype "bidirectional"))
    )
    (net (code "80") (name "Net-(U1-PA3_(AD3))") (class "Default")
      (node (ref "R9") (pin "2") (pinfunction "2_2") (pintype "passive"))
      (node (ref "U1") (pin "48") (pinfunction "PA3_(AD3)_48") (pintype "bidirectional"))
    )
    (net (code "81") (name "Net-(U1-PA4_(AD4))") (class "Default")
      (node (ref "R11") (pin "1") (pinfunction "1_1") (pintype "passive"))
      (node (ref "U1") (pin "47") (pinfunction "PA4_(AD4)_47") (pintype "bidirectional"))
    )
    (net (code "82") (name "Net-(U1-PA5_(AD5))") (class "Default")
      (node (ref "R14") (pin "1") (pinfunction "1_1") (pintype "passive"))
      (node (ref "U1") (pin "46") (pinfunction "PA5_(AD5)_46") (pintype "bidirectional"))
    )
    (net (code "83") (name "Net-(U1-PA6_(AD6))") (class "Default")
      (node (ref "R13") (pin "1") (pinfunction "1_1") (pintype "passive"))
      (node (ref "U1") (pin "45") (pinfunction "PA6_(AD6)_45") (pintype "bidirectional"))
    )
    (net (code "84") (name "Net-(U1-PA7_(AD7))") (class "Default")
      (node (ref "R16") (pin "1") (pinfunction "1_1") (pintype "passive"))
      (node (ref "U1") (pin "44") (pinfunction "PA7_(AD7)_44") (pintype "bidirectional"))
    )
    (net (code "85") (name "Net-(U1-PC0_(A8))") (class "Default")
      (node (ref "R19") (pin "2") (pinfunction "2_2") (pintype "passive"))
      (node (ref "U1") (pin "35") (pinfunction "PC0_(A8)_35") (pintype "bidirectional"))
    )
    (net (code "86") (name "Net-(U1-PC1_(A9))") (class "Default")
      (node (ref "R21") (pin "2") (pinfunction "2_2") (pintype "passive"))
      (node (ref "U1") (pin "36") (pinfunction "PC1_(A9)_36") (pintype "bidirectional"))
    )
    (net (code "87") (name "Net-(U1-PC2_(A10))") (class "Default")
      (node (ref "R27") (pin "1") (pinfunction "1_1") (pintype "passive"))
      (node (ref "U1") (pin "37") (pinfunction "PC2_(A10)_37") (pintype "bidirectional"))
    )
    (net (code "88") (name "Net-(U1-PC3_(A11))") (class "Default")
      (node (ref "R25") (pin "1") (pinfunction "1_1") (pintype "passive"))
      (node (ref "U1") (pin "38") (pinfunction "PC3_(A11)_38") (pintype "bidirectional"))
    )
    (net (code "89") (name "Net-(U1-PC4_(A12))") (class "Default")
      (node (ref "R46") (pin "2") (pinfunction "2_2") (pintype "passive"))
      (node (ref "U1") (pin "39") (pinfunction "PC4_(A12)_39") (pintype "bidirectional"))
    )
    (net (code "90") (name "Net-(U1-PC5_(A13))") (class "Default")
      (node (ref "R48") (pin "2") (pinfunction "2_2") (pintype "passive"))
      (node (ref "U1") (pin "40") (pinfunction "PC5_(A13)_40") (pintype "bidirectional"))
    )
    (net (code "91") (name "Net-(U1-PC6_(A14))") (class "Default")
      (node (ref "R50") (pin "2") (pinfunction "2_2") (pintype "passive"))
      (node (ref "U1") (pin "41") (pinfunction "PC6_(A14)_41") (pintype "bidirectional"))
    )
    (net (code "92") (name "Net-(U1-PC7_(A15_{slash}_CLKO))") (class "Default")
      (node (ref "R52") (pin "2") (pinfunction "2_2") (pintype "passive"))
      (node (ref "U1") (pin "42") (pinfunction "PC7_(A15_/_CLKO)_42") (pintype "bidirectional"))
    )
    (net (code "93") (name "Net-(U1-PF0_(ADC0))") (class "Default")
      (node (ref "R17") (pin "2") (pinfunction "2_2") (pintype "passive"))
      (node (ref "U1") (pin "61") (pinfunction "PF0_(ADC0)_61") (pintype "bidirectional"))
    )
    (net (code "94") (name "Net-(U1-PF1_(ADC1))") (class "Default")
      (node (ref "R15") (pin "2") (pinfunction "2_2") (pintype "passive"))
      (node (ref "U1") (pin "60") (pinfunction "PF1_(ADC1)_60") (pintype "bidirectional"))
    )
    (net (code "95") (name "Net-(U1-PF2_(ADC2))") (class "Default")
      (node (ref "R23") (pin "1") (pinfunction "1_1") (pintype "passive"))
      (node (ref "U1") (pin "59") (pinfunction "PF2_(ADC2)_59") (pintype "bidirectional"))
    )
    (net (code "96") (name "Net-(U1-PF3_(ADC3))") (class "Default")
      (node (ref "R12") (pin "2") (pinfunction "2_2") (pintype "passive"))
      (node (ref "U1") (pin "58") (pinfunction "PF3_(ADC3)_58") (pintype "bidirectional"))
    )
    (net (code "97") (name "Net-(U1-PG0_(~{WR)})") (class "Default")
      (node (ref "R1") (pin "2") (pinfunction "2_2") (pintype "passive"))
      (node (ref "U1") (pin "33") (pinfunction "PG0_(~{WR)}_33") (pintype "bidirectional"))
    )
    (net (code "98") (name "Net-(U1-PG1_(~{RD)})") (class "Default")
      (node (ref "R2") (pin "2") (pinfunction "2_2") (pintype "passive"))
      (node (ref "U1") (pin "34") (pinfunction "PG1_(~{RD)}_34") (pintype "bidirectional"))
    )
    (net (code "99") (name "Net-(U1-PG2_(ALE))") (class "Default")
      (node (ref "R5") (pin "2") (pinfunction "2_2") (pintype "passive"))
      (node (ref "U1") (pin "43") (pinfunction "PG2_(ALE)_43") (pintype "bidirectional"))
    )
    (net (code "100") (name "Net-(U1-XTAL1)") (class "Default")
      (node (ref "C6") (pin "2") (pinfunction "2_2") (pintype "passive"))
      (node (ref "Q1") (pin "1") (pinfunction "1_1") (pintype "passive"))
      (node (ref "U1") (pin "24") (pinfunction "XTAL1_24") (pintype "input"))
    )
    (net (code "101") (name "Net-(U1-XTAL2)") (class "Default")
      (node (ref "C1") (pin "2") (pinfunction "2_2") (pintype "passive"))
      (node (ref "Q1") (pin "2") (pinfunction "2_2") (pintype "passive"))
      (node (ref "U1") (pin "23") (pinfunction "XTAL2_23") (pintype "output"))
    )
    (net (code "102") (name "Net-(U3-RS)") (class "Default")
      (node (ref "CCTRL1") (pin "2") (pinfunction "2_2") (pintype "passive"))
      (node (ref "R40") (pin "2") (pinfunction "2_2") (pintype "passive"))
      (node (ref "U3") (pin "8") (pinfunction "RS_8") (pintype "input"))
    )
    (net (code "103") (name "Net-(U3-VREF)") (class "Default")
      (node (ref "R35") (pin "1") (pinfunction "1_1") (pintype "passive"))
      (node (ref "U3") (pin "5") (pinfunction "VREF_5") (pintype "output"))
    )
    (net (code "104") (name "unconnected-(CAN_3-MH1-Pad5)") (class "Default")
      (node (ref "CAN_3") (pin "5") (pinfunction "MH1_5") (pintype "passive"))
    )
    (net (code "105") (name "unconnected-(CAN_3-MH2-Pad6)") (class "Default")
      (node (ref "CAN_3") (pin "6") (pinfunction "MH2_6") (pintype "passive"))
    )
    (net (code "106") (name "unconnected-(DIC-MH1-Pad5)") (class "Default")
      (node (ref "DIC") (pin "5") (pinfunction "MH1_5") (pintype "passive"))
    )
    (net (code "107") (name "unconnected-(DIC-MH2-Pad6)") (class "Default")
      (node (ref "DIC") (pin "6") (pinfunction "MH2_6") (pintype "passive"))
    )
    (net (code "108") (name "unconnected-(Display1-Pad3)") (class "Default")
      (node (ref "Display1") (pin "3") (pinfunction "3_3") (pintype "bidirectional+no_connect"))
    )
    (net (code "109") (name "unconnected-(Display1-Pad15)") (class "Default")
      (node (ref "Display1") (pin "15") (pinfunction "15_15") (pintype "bidirectional+no_connect"))
    )
    (net (code "110") (name "unconnected-(Display1-Pad16)") (class "Default")
      (node (ref "Display1") (pin "16") (pinfunction "16_16") (pintype "bidirectional+no_connect"))
    )
    (net (code "111") (name "unconnected-(JTAG1-Pad8)") (class "Default")
      (node (ref "JTAG1") (pin "8") (pinfunction "8_8") (pintype "passive"))
    )
    (net (code "112") (name "unconnected-(SD_TS-MH1-Pad11)") (class "Default")
      (node (ref "SD_TS") (pin "11") (pinfunction "MH1_11") (pintype "passive"))
    )
    (net (code "113") (name "unconnected-(SD_TS-MH2-Pad12)") (class "Default")
      (node (ref "SD_TS") (pin "12") (pinfunction "MH2_12") (pintype "passive"))
    )
    (net (code "114") (name "unconnected-(SD_TS-Pad6)") (class "Default")
      (node (ref "SD_TS") (pin "6") (pinfunction "6_6") (pintype "passive"))
    )
    (net (code "115") (name "unconnected-(SWC-MH1-Pad5)") (class "Default")
      (node (ref "SWC") (pin "5") (pinfunction "MH1_5") (pintype "passive"))
    )
    (net (code "116") (name "unconnected-(SWC-MH2-Pad6)") (class "Default")
      (node (ref "SWC") (pin "6") (pinfunction "MH2_6") (pintype "passive"))
    )
    (net (code "117") (name "unconnected-(U1-NC-Pad1)") (class "Default")
      (node (ref "U1") (pin "1") (pinfunction "NC_1") (pintype "passive"))
    )
  )
)
